# tides_v40.net
KiCad netlist of a schematic drawn in EAGLE
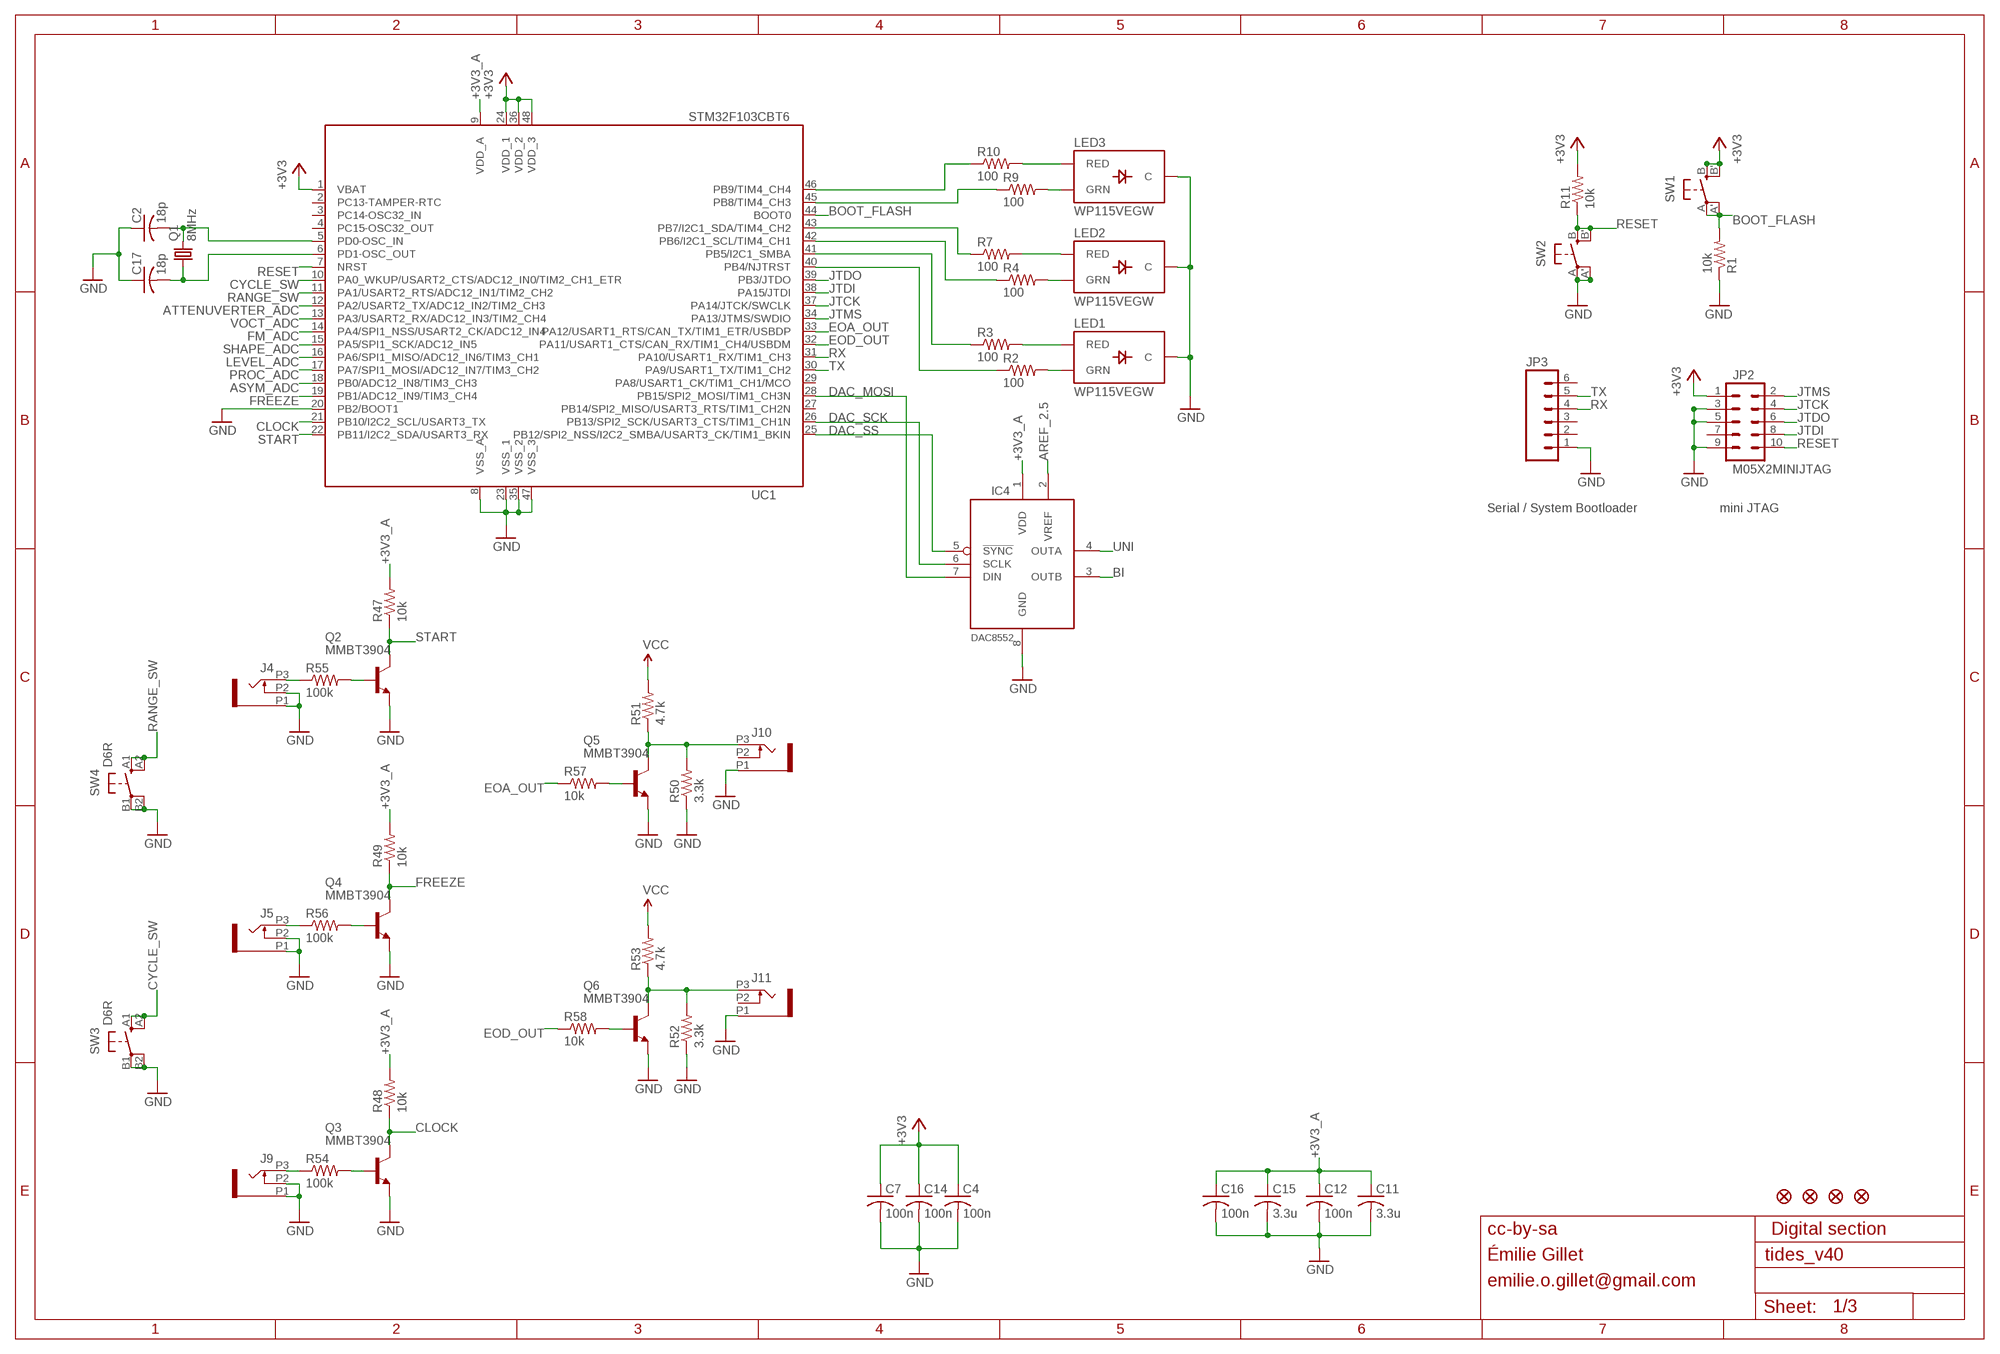
[diagram p0: schematic, sheet 1]
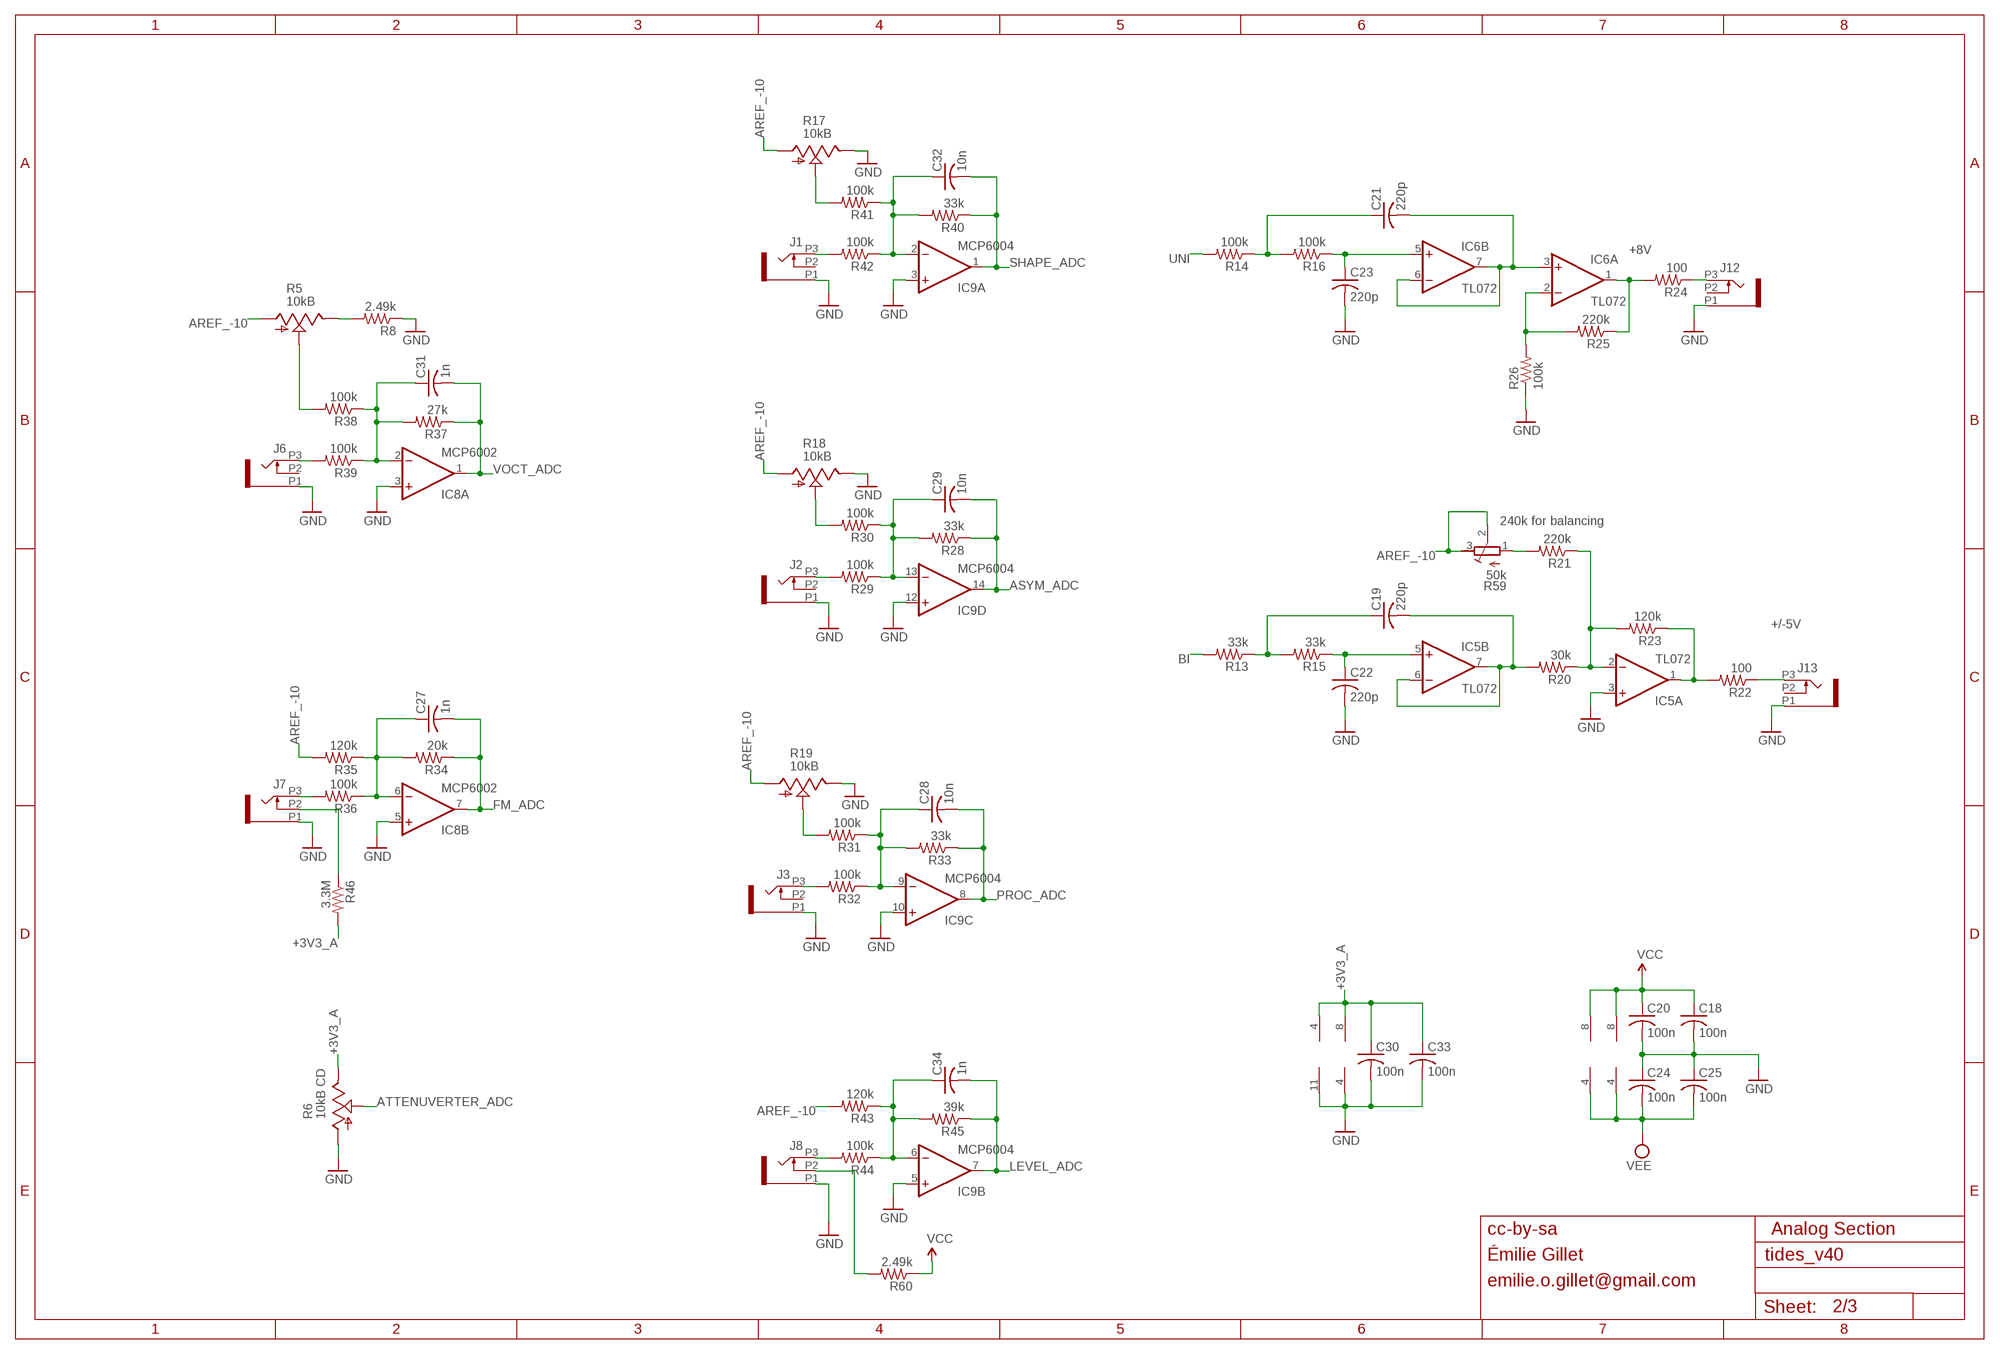
[diagram p1: schematic, sheet 2]
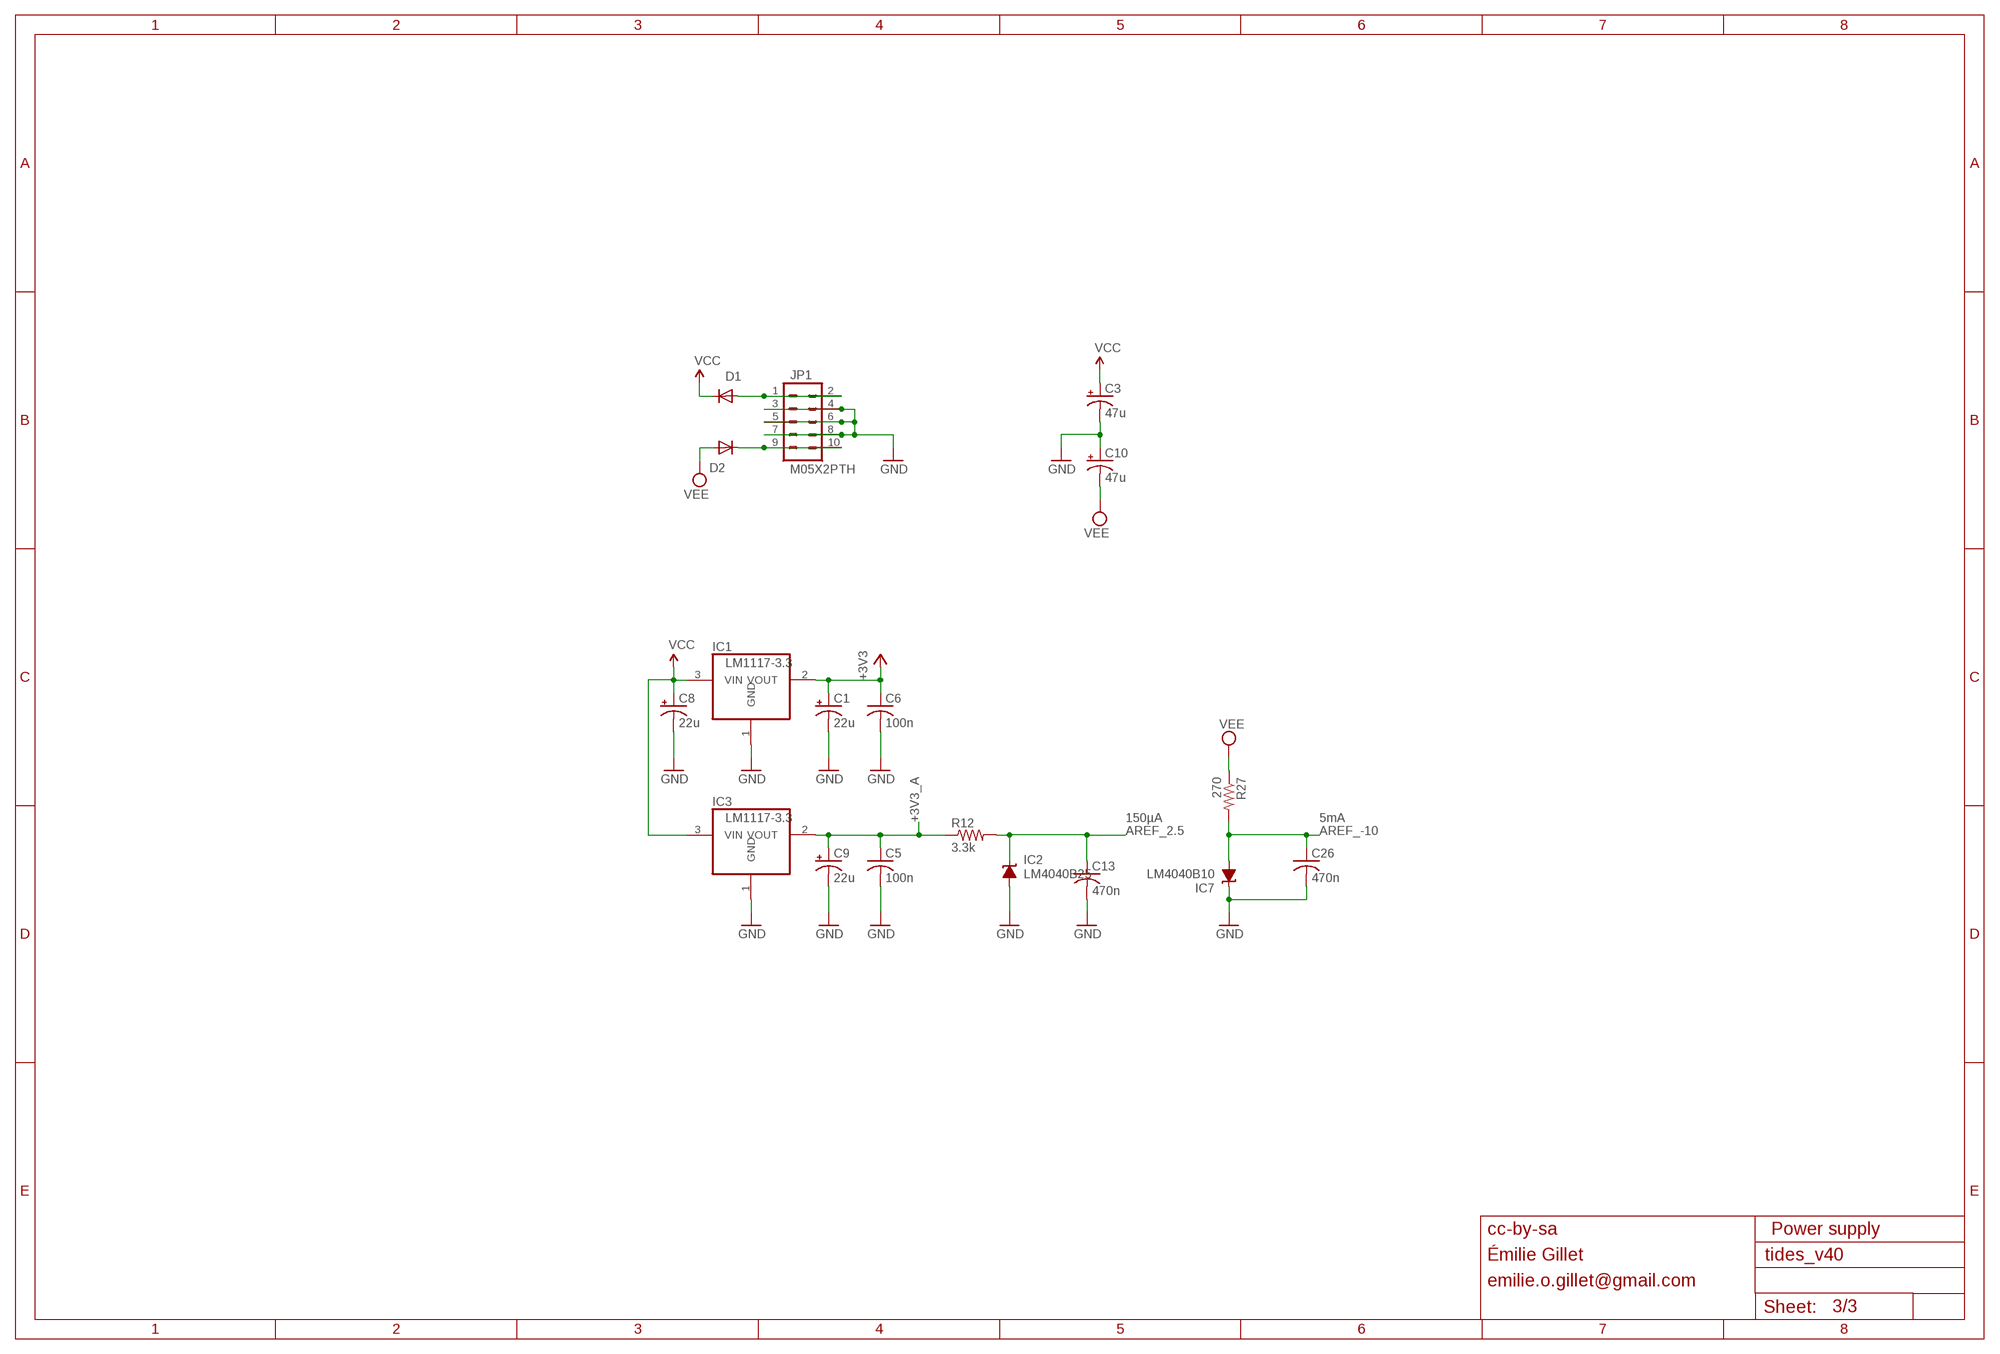
[diagram p2: schematic, sheet 3]

(export (version "E")
  (design (tool "Eeschema 10.0.6"))
  (components
    (comp (ref "C2")
      (value "18p")
      (footprint "eagle-import:C0603")
      (libsource (lib "eagle-import") (part "C-USC0603"))
    )
    (comp (ref "C4")
      (value "100n")
      (footprint "eagle-import:C0603")
      (libsource (lib "eagle-import") (part "C-USC0603"))
    )
    (comp (ref "C7")
      (value "100n")
      (footprint "eagle-import:C0603")
      (libsource (lib "eagle-import") (part "C-USC0603"))
    )
    (comp (ref "C11")
      (value "3.3u")
      (footprint "eagle-import:C0603")
      (libsource (lib "eagle-import") (part "C-USC0603"))
    )
    (comp (ref "C12")
      (value "100n")
      (footprint "eagle-import:C0603")
      (libsource (lib "eagle-import") (part "C-USC0603"))
    )
    (comp (ref "C14")
      (value "100n")
      (footprint "eagle-import:C0603")
      (libsource (lib "eagle-import") (part "C-USC0603"))
    )
    (comp (ref "C15")
      (value "3.3u")
      (footprint "eagle-import:C0603")
      (libsource (lib "eagle-import") (part "C-USC0603"))
    )
    (comp (ref "C16")
      (value "100n")
      (footprint "eagle-import:C0603")
      (libsource (lib "eagle-import") (part "C-USC0603"))
    )
    (comp (ref "C17")
      (value "18p")
      (footprint "eagle-import:C0603")
      (libsource (lib "eagle-import") (part "C-USC0603"))
    )
    (comp (ref "IC4")
      (value "DAC8552")
      (footprint "eagle-import:MSOP-8")
      (libsource (lib "eagle-import") (part "DAC8552"))
    )
    (comp (ref "J4")
      (value "PJ301_THONKICONN6")
      (footprint "eagle-import:WQP_PJ_301M6")
      (libsource (lib "eagle-import") (part "PJ301_THONKICONN6"))
    )
    (comp (ref "J5")
      (value "PJ301_THONKICONN6")
      (footprint "eagle-import:WQP_PJ_301M6")
      (libsource (lib "eagle-import") (part "PJ301_THONKICONN6"))
    )
    (comp (ref "J9")
      (value "PJ301_THONKICONN6")
      (footprint "eagle-import:WQP_PJ_301M6")
      (libsource (lib "eagle-import") (part "PJ301_THONKICONN6"))
    )
    (comp (ref "J10")
      (value "PJ301_THONKICONN6")
      (footprint "eagle-import:WQP_PJ_301M6")
      (libsource (lib "eagle-import") (part "PJ301_THONKICONN6"))
    )
    (comp (ref "J11")
      (value "PJ301_THONKICONN6")
      (footprint "eagle-import:WQP_PJ_301M6")
      (libsource (lib "eagle-import") (part "PJ301_THONKICONN6"))
    )
    (comp (ref "JP2")
      (value "M05X2MINIJTAG")
      (footprint "eagle-import:2X5-1.27")
      (libsource (lib "eagle-import") (part "M05X2MINIJTAG"))
    )
    (comp (ref "JP3")
      (value "M06SIP")
      (footprint "eagle-import:1X06")
      (libsource (lib "eagle-import") (part "M06SIP"))
    )
    (comp (ref "JP4")
      (value "FIDUCIAL1X2")
      (footprint "eagle-import:FIDUCIAL-1X2")
      (libsource (lib "eagle-import") (part "FIDUCIAL1X2"))
    )
    (comp (ref "JP5")
      (value "FIDUCIAL1X2")
      (footprint "eagle-import:FIDUCIAL-1X2")
      (libsource (lib "eagle-import") (part "FIDUCIAL1X2"))
    )
    (comp (ref "JP6")
      (value "FIDUCIAL1X2")
      (footprint "eagle-import:FIDUCIAL-1X2")
      (libsource (lib "eagle-import") (part "FIDUCIAL1X2"))
    )
    (comp (ref "JP7")
      (value "FIDUCIAL1X2")
      (footprint "eagle-import:FIDUCIAL-1X2")
      (libsource (lib "eagle-import") (part "FIDUCIAL1X2"))
    )
    (comp (ref "LED1")
      (value "WP115VEGW")
      (footprint "eagle-import:LED-BICOLOR-THROUGHHOLE")
      (libsource (lib "eagle-import") (part "LED-BICOLOR-THROUGHHOLE"))
    )
    (comp (ref "LED2")
      (value "WP115VEGW")
      (footprint "eagle-import:LED-BICOLOR-THROUGHHOLE")
      (libsource (lib "eagle-import") (part "LED-BICOLOR-THROUGHHOLE"))
    )
    (comp (ref "LED3")
      (value "WP115VEGW")
      (footprint "eagle-import:LED-BICOLOR-THROUGHHOLE")
      (libsource (lib "eagle-import") (part "LED-BICOLOR-THROUGHHOLE"))
    )
    (comp (ref "Q1")
      (value "8MHz")
      (footprint "eagle-import:HC49UP")
      (libsource (lib "eagle-import") (part "CRYSTALHC49UP"))
    )
    (comp (ref "Q2")
      (value "MMBT3904")
      (footprint "eagle-import:SOT23-BEC")
      (libsource (lib "eagle-import") (part "-NPN-SOT23-BECMMBT3904LT1"))
    )
    (comp (ref "Q3")
      (value "MMBT3904")
      (footprint "eagle-import:SOT23-BEC")
      (libsource (lib "eagle-import") (part "-NPN-SOT23-BECMMBT3904LT1"))
    )
    (comp (ref "Q4")
      (value "MMBT3904")
      (footprint "eagle-import:SOT23-BEC")
      (libsource (lib "eagle-import") (part "-NPN-SOT23-BECMMBT3904LT1"))
    )
    (comp (ref "Q5")
      (value "MMBT3904")
      (footprint "eagle-import:SOT23-BEC")
      (libsource (lib "eagle-import") (part "-NPN-SOT23-BECMMBT3904LT1"))
    )
    (comp (ref "Q6")
      (value "MMBT3904")
      (footprint "eagle-import:SOT23-BEC")
      (libsource (lib "eagle-import") (part "-NPN-SOT23-BECMMBT3904LT1"))
    )
    (comp (ref "R1")
      (value "10k")
      (footprint "eagle-import:R0603")
      (libsource (lib "eagle-import") (part "R-US_R0603"))
    )
    (comp (ref "R2")
      (value "100")
      (footprint "eagle-import:R0603")
      (libsource (lib "eagle-import") (part "R-US_R0603"))
    )
    (comp (ref "R3")
      (value "100")
      (footprint "eagle-import:R0603")
      (libsource (lib "eagle-import") (part "R-US_R0603"))
    )
    (comp (ref "R4")
      (value "100")
      (footprint "eagle-import:R0603")
      (libsource (lib "eagle-import") (part "R-US_R0603"))
    )
    (comp (ref "R7")
      (value "100")
      (footprint "eagle-import:R0603")
      (libsource (lib "eagle-import") (part "R-US_R0603"))
    )
    (comp (ref "R9")
      (value "100")
      (footprint "eagle-import:R0603")
      (libsource (lib "eagle-import") (part "R-US_R0603"))
    )
    (comp (ref "R10")
      (value "100")
      (footprint "eagle-import:R0603")
      (libsource (lib "eagle-import") (part "R-US_R0603"))
    )
    (comp (ref "R11")
      (value "10k")
      (footprint "eagle-import:R0603")
      (libsource (lib "eagle-import") (part "R-US_R0603"))
    )
    (comp (ref "R47")
      (value "10k")
      (footprint "eagle-import:R0603")
      (libsource (lib "eagle-import") (part "R-US_R0603"))
    )
    (comp (ref "R48")
      (value "10k")
      (footprint "eagle-import:R0603")
      (libsource (lib "eagle-import") (part "R-US_R0603"))
    )
    (comp (ref "R49")
      (value "10k")
      (footprint "eagle-import:R0603")
      (libsource (lib "eagle-import") (part "R-US_R0603"))
    )
    (comp (ref "R50")
      (value "3.3k")
      (footprint "eagle-import:R0603")
      (libsource (lib "eagle-import") (part "R-US_R0603"))
    )
    (comp (ref "R51")
      (value "4.7k")
      (footprint "eagle-import:R0603")
      (libsource (lib "eagle-import") (part "R-US_R0603"))
    )
    (comp (ref "R52")
      (value "3.3k")
      (footprint "eagle-import:R0603")
      (libsource (lib "eagle-import") (part "R-US_R0603"))
    )
    (comp (ref "R53")
      (value "4.7k")
      (footprint "eagle-import:R0603")
      (libsource (lib "eagle-import") (part "R-US_R0603"))
    )
    (comp (ref "R54")
      (value "100k")
      (footprint "eagle-import:R0603")
      (libsource (lib "eagle-import") (part "R-US_R0603"))
    )
    (comp (ref "R55")
      (value "100k")
      (footprint "eagle-import:R0603")
      (libsource (lib "eagle-import") (part "R-US_R0603"))
    )
    (comp (ref "R56")
      (value "100k")
      (footprint "eagle-import:R0603")
      (libsource (lib "eagle-import") (part "R-US_R0603"))
    )
    (comp (ref "R57")
      (value "10k")
      (footprint "eagle-import:R0603")
      (libsource (lib "eagle-import") (part "R-US_R0603"))
    )
    (comp (ref "R58")
      (value "10k")
      (footprint "eagle-import:R0603")
      (libsource (lib "eagle-import") (part "R-US_R0603"))
    )
    (comp (ref "SW1")
      (value "EVQQ2")
      (footprint "eagle-import:EVQ-Q2")
      (libsource (lib "eagle-import") (part "EVQQ2"))
    )
    (comp (ref "SW2")
      (value "EVQQ2")
      (footprint "eagle-import:EVQ-Q2")
      (libsource (lib "eagle-import") (part "EVQQ2"))
    )
    (comp (ref "SW3")
      (value "D6R")
      (footprint "eagle-import:D6R")
      (libsource (lib "eagle-import") (part "D6R"))
    )
    (comp (ref "SW4")
      (value "D6R")
      (footprint "eagle-import:D6R")
      (libsource (lib "eagle-import") (part "D6R"))
    )
    (comp (ref "UC1")
      (value "STM32F103CBT6")
      (footprint "eagle-import:LQFP48")
      (libsource (lib "eagle-import") (part "STM32F103CB"))
    )
    (comp (ref "C18")
      (value "100n")
      (footprint "eagle-import:C0603")
      (libsource (lib "eagle-import") (part "C-USC0603"))
    )
    (comp (ref "C19")
      (value "220p")
      (footprint "eagle-import:C0603")
      (libsource (lib "eagle-import") (part "C-USC0603"))
    )
    (comp (ref "C20")
      (value "100n")
      (footprint "eagle-import:C0603")
      (libsource (lib "eagle-import") (part "C-USC0603"))
    )
    (comp (ref "C21")
      (value "220p")
      (footprint "eagle-import:C0603")
      (libsource (lib "eagle-import") (part "C-USC0603"))
    )
    (comp (ref "C22")
      (value "220p")
      (footprint "eagle-import:C0603")
      (libsource (lib "eagle-import") (part "C-USC0603"))
    )
    (comp (ref "C23")
      (value "220p")
      (footprint "eagle-import:C0603")
      (libsource (lib "eagle-import") (part "C-USC0603"))
    )
    (comp (ref "C24")
      (value "100n")
      (footprint "eagle-import:C0603")
      (libsource (lib "eagle-import") (part "C-USC0603"))
    )
    (comp (ref "C25")
      (value "100n")
      (footprint "eagle-import:C0603")
      (libsource (lib "eagle-import") (part "C-USC0603"))
    )
    (comp (ref "C27")
      (value "1n")
      (footprint "eagle-import:C0603")
      (libsource (lib "eagle-import") (part "C-USC0603"))
    )
    (comp (ref "C28")
      (value "10n")
      (footprint "eagle-import:C0603")
      (libsource (lib "eagle-import") (part "C-USC0603"))
    )
    (comp (ref "C29")
      (value "10n")
      (footprint "eagle-import:C0603")
      (libsource (lib "eagle-import") (part "C-USC0603"))
    )
    (comp (ref "C30")
      (value "100n")
      (footprint "eagle-import:C0603")
      (libsource (lib "eagle-import") (part "C-USC0603"))
    )
    (comp (ref "C31")
      (value "1n")
      (footprint "eagle-import:C0603")
      (libsource (lib "eagle-import") (part "C-USC0603"))
    )
    (comp (ref "C32")
      (value "10n")
      (footprint "eagle-import:C0603")
      (libsource (lib "eagle-import") (part "C-USC0603"))
    )
    (comp (ref "C33")
      (value "100n")
      (footprint "eagle-import:C0603")
      (libsource (lib "eagle-import") (part "C-USC0603"))
    )
    (comp (ref "C34")
      (value "1n")
      (footprint "eagle-import:C0603")
      (libsource (lib "eagle-import") (part "C-USC0603"))
    )
    (comp (ref "IC5")
      (value "TL072")
      (footprint "eagle-import:SO08")
      (libsource (lib "eagle-import") (part "TL072D"))
    )
    (comp (ref "IC6")
      (value "TL072")
      (footprint "eagle-import:SO08")
      (libsource (lib "eagle-import") (part "TL072D"))
    )
    (comp (ref "IC8")
      (value "MCP6002")
      (footprint "eagle-import:SO08")
      (libsource (lib "eagle-import") (part "TL072D"))
    )
    (comp (ref "IC9")
      (value "MCP6004")
      (footprint "eagle-import:SO14")
      (libsource (lib "eagle-import") (part "TL074D"))
    )
    (comp (ref "J1")
      (value "PJ301_THONKICONN6")
      (footprint "eagle-import:WQP_PJ_301M6")
      (libsource (lib "eagle-import") (part "PJ301_THONKICONN6"))
    )
    (comp (ref "J2")
      (value "PJ301_THONKICONN6")
      (footprint "eagle-import:WQP_PJ_301M6")
      (libsource (lib "eagle-import") (part "PJ301_THONKICONN6"))
    )
    (comp (ref "J3")
      (value "PJ301_THONKICONN6")
      (footprint "eagle-import:WQP_PJ_301M6")
      (libsource (lib "eagle-import") (part "PJ301_THONKICONN6"))
    )
    (comp (ref "J6")
      (value "PJ301_THONKICONN6")
      (footprint "eagle-import:WQP_PJ_301M6")
      (libsource (lib "eagle-import") (part "PJ301_THONKICONN6"))
    )
    (comp (ref "J7")
      (value "PJ301_THONKICONN6")
      (footprint "eagle-import:WQP_PJ_301M6")
      (libsource (lib "eagle-import") (part "PJ301_THONKICONN6"))
    )
    (comp (ref "J8")
      (value "PJ301_THONKICONN6")
      (footprint "eagle-import:WQP_PJ_301M6")
      (libsource (lib "eagle-import") (part "PJ301_THONKICONN6"))
    )
    (comp (ref "J12")
      (value "PJ301_THONKICONN6")
      (footprint "eagle-import:WQP_PJ_301M6")
      (libsource (lib "eagle-import") (part "PJ301_THONKICONN6"))
    )
    (comp (ref "J13")
      (value "PJ301_THONKICONN6")
      (footprint "eagle-import:WQP_PJ_301M6")
      (libsource (lib "eagle-import") (part "PJ301_THONKICONN6"))
    )
    (comp (ref "R5")
      (value "10kB")
      (footprint "eagle-import:ALPS_POT_VERTICAL_PS")
      (libsource (lib "eagle-import") (part "POT_USVERTICAL_PS"))
    )
    (comp (ref "R6")
      (value "10kB CD")
      (footprint "eagle-import:ALPS_POT_VERTICAL_PS")
      (libsource (lib "eagle-import") (part "POT_USVERTICAL_PS"))
    )
    (comp (ref "R8")
      (value "2.49k")
      (footprint "eagle-import:R0603")
      (libsource (lib "eagle-import") (part "R-US_R0603"))
    )
    (comp (ref "R13")
      (value "33k")
      (footprint "eagle-import:R0603")
      (libsource (lib "eagle-import") (part "R-US_R0603"))
    )
    (comp (ref "R14")
      (value "100k")
      (footprint "eagle-import:R0603")
      (libsource (lib "eagle-import") (part "R-US_R0603"))
    )
    (comp (ref "R15")
      (value "33k")
      (footprint "eagle-import:R0603")
      (libsource (lib "eagle-import") (part "R-US_R0603"))
    )
    (comp (ref "R16")
      (value "100k")
      (footprint "eagle-import:R0603")
      (libsource (lib "eagle-import") (part "R-US_R0603"))
    )
    (comp (ref "R17")
      (value "10kB")
      (footprint "eagle-import:ALPS_POT_VERTICAL_PS")
      (libsource (lib "eagle-import") (part "POT_USVERTICAL_PS"))
    )
    (comp (ref "R18")
      (value "10kB")
      (footprint "eagle-import:ALPS_POT_VERTICAL_PS")
      (libsource (lib "eagle-import") (part "POT_USVERTICAL_PS"))
    )
    (comp (ref "R19")
      (value "10kB")
      (footprint "eagle-import:ALPS_POT_VERTICAL_PS")
      (libsource (lib "eagle-import") (part "POT_USVERTICAL_PS"))
    )
    (comp (ref "R20")
      (value "30k")
      (footprint "eagle-import:R0603")
      (libsource (lib "eagle-import") (part "R-US_R0603"))
    )
    (comp (ref "R21")
      (value "220k")
      (footprint "eagle-import:R0603")
      (libsource (lib "eagle-import") (part "R-US_R0603"))
    )
    (comp (ref "R22")
      (value "100")
      (footprint "eagle-import:R0603")
      (libsource (lib "eagle-import") (part "R-US_R0603"))
    )
    (comp (ref "R23")
      (value "120k")
      (footprint "eagle-import:R0603")
      (libsource (lib "eagle-import") (part "R-US_R0603"))
    )
    (comp (ref "R24")
      (value "100")
      (footprint "eagle-import:R0603")
      (libsource (lib "eagle-import") (part "R-US_R0603"))
    )
    (comp (ref "R25")
      (value "220k")
      (footprint "eagle-import:R0603")
      (libsource (lib "eagle-import") (part "R-US_R0603"))
    )
    (comp (ref "R26")
      (value "100k")
      (footprint "eagle-import:R0603")
      (libsource (lib "eagle-import") (part "R-US_R0603"))
    )
    (comp (ref "R28")
      (value "33k")
      (footprint "eagle-import:R0603")
      (libsource (lib "eagle-import") (part "R-US_R0603"))
    )
    (comp (ref "R29")
      (value "100k")
      (footprint "eagle-import:R0603")
      (libsource (lib "eagle-import") (part "R-US_R0603"))
    )
    (comp (ref "R30")
      (value "100k")
      (footprint "eagle-import:R0603")
      (libsource (lib "eagle-import") (part "R-US_R0603"))
    )
    (comp (ref "R31")
      (value "100k")
      (footprint "eagle-import:R0603")
      (libsource (lib "eagle-import") (part "R-US_R0603"))
    )
    (comp (ref "R32")
      (value "100k")
      (footprint "eagle-import:R0603")
      (libsource (lib "eagle-import") (part "R-US_R0603"))
    )
    (comp (ref "R33")
      (value "33k")
      (footprint "eagle-import:R0603")
      (libsource (lib "eagle-import") (part "R-US_R0603"))
    )
    (comp (ref "R34")
      (value "20k")
      (footprint "eagle-import:R0603")
      (libsource (lib "eagle-import") (part "R-US_R0603"))
    )
    (comp (ref "R35")
      (value "120k")
      (footprint "eagle-import:R0603")
      (libsource (lib "eagle-import") (part "R-US_R0603"))
    )
    (comp (ref "R36")
      (value "100k")
      (footprint "eagle-import:R0603")
      (libsource (lib "eagle-import") (part "R-US_R0603"))
    )
    (comp (ref "R37")
      (value "27k")
      (footprint "eagle-import:R0603")
      (libsource (lib "eagle-import") (part "R-US_R0603"))
    )
    (comp (ref "R38")
      (value "100k")
      (footprint "eagle-import:R0603")
      (libsource (lib "eagle-import") (part "R-US_R0603"))
    )
    (comp (ref "R39")
      (value "100k")
      (footprint "eagle-import:R0603")
      (libsource (lib "eagle-import") (part "R-US_R0603"))
    )
    (comp (ref "R40")
      (value "33k")
      (footprint "eagle-import:R0603")
      (libsource (lib "eagle-import") (part "R-US_R0603"))
    )
    (comp (ref "R41")
      (value "100k")
      (footprint "eagle-import:R0603")
      (libsource (lib "eagle-import") (part "R-US_R0603"))
    )
    (comp (ref "R42")
      (value "100k")
      (footprint "eagle-import:R0603")
      (libsource (lib "eagle-import") (part "R-US_R0603"))
    )
    (comp (ref "R43")
      (value "120k")
      (footprint "eagle-import:R0603")
      (libsource (lib "eagle-import") (part "R-US_R0603"))
    )
    (comp (ref "R44")
      (value "100k")
      (footprint "eagle-import:R0603")
      (libsource (lib "eagle-import") (part "R-US_R0603"))
    )
    (comp (ref "R45")
      (value "39k")
      (footprint "eagle-import:R0603")
      (libsource (lib "eagle-import") (part "R-US_R0603"))
    )
    (comp (ref "R46")
      (value "3.3M")
      (footprint "eagle-import:R0603")
      (libsource (lib "eagle-import") (part "R-US_R0603"))
    )
    (comp (ref "R59")
      (value "50k")
      (footprint "eagle-import:RTRIM3296X")
      (libsource (lib "eagle-import") (part "R-TRIMM3296X"))
    )
    (comp (ref "R60")
      (value "2.49k")
      (footprint "eagle-import:R0805")
      (libsource (lib "eagle-import") (part "R-US_R0805"))
    )
    (comp (ref "C1")
      (value "22u")
      (footprint "eagle-import:PANASONIC_C")
      (libsource (lib "eagle-import") (part "CPOL-USC"))
    )
    (comp (ref "C3")
      (value "47u")
      (footprint "eagle-import:PANASONIC_D")
      (libsource (lib "eagle-import") (part "CPOL-USD"))
    )
    (comp (ref "C5")
      (value "100n")
      (footprint "eagle-import:C0603")
      (libsource (lib "eagle-import") (part "C-USC0603"))
    )
    (comp (ref "C6")
      (value "100n")
      (footprint "eagle-import:C0603")
      (libsource (lib "eagle-import") (part "C-USC0603"))
    )
    (comp (ref "C8")
      (value "22u")
      (footprint "eagle-import:PANASONIC_C")
      (libsource (lib "eagle-import") (part "CPOL-USC"))
    )
    (comp (ref "C9")
      (value "22u")
      (footprint "eagle-import:PANASONIC_C")
      (libsource (lib "eagle-import") (part "CPOL-USC"))
    )
    (comp (ref "C10")
      (value "47u")
      (footprint "eagle-import:PANASONIC_D")
      (libsource (lib "eagle-import") (part "CPOL-USD"))
    )
    (comp (ref "C13")
      (value "470n")
      (footprint "eagle-import:C0603")
      (libsource (lib "eagle-import") (part "C-USC0603"))
    )
    (comp (ref "C26")
      (value "470n")
      (footprint "eagle-import:C0603")
      (libsource (lib "eagle-import") (part "C-USC0603"))
    )
    (comp (ref "D1")
      (value "1N5819HW")
      (footprint "eagle-import:SOD123")
      (libsource (lib "eagle-import") (part "DIODE-SOD123"))
    )
    (comp (ref "D2")
      (value "1N5819HW")
      (footprint "eagle-import:SOD123")
      (libsource (lib "eagle-import") (part "DIODE-SOD123"))
    )
    (comp (ref "IC1")
      (value "LM1117-3.3")
      (footprint "eagle-import:SOT223")
      (libsource (lib "eagle-import") (part "REG1117"))
    )
    (comp (ref "IC2")
      (value "LM4040B25")
      (footprint "eagle-import:DBZ_R-PDSO-G3")
      (libsource (lib "eagle-import") (part "LM4041DBZB12"))
    )
    (comp (ref "IC3")
      (value "LM1117-3.3")
      (footprint "eagle-import:SOT223")
      (libsource (lib "eagle-import") (part "REG1117"))
    )
    (comp (ref "IC7")
      (value "LM4040B10")
      (footprint "eagle-import:DBZ_R-PDSO-G3")
      (libsource (lib "eagle-import") (part "LM4041DBZB12"))
    )
    (comp (ref "JP1")
      (value "M05X2PTH")
      (footprint "eagle-import:AVR_ICSP")
      (libsource (lib "eagle-import") (part "M05X2PTH"))
    )
    (comp (ref "R12")
      (value "3.3k")
      (footprint "eagle-import:R0603")
      (libsource (lib "eagle-import") (part "R-US_R0603"))
    )
    (comp (ref "R27")
      (value "270")
      (footprint "eagle-import:R0603")
      (libsource (lib "eagle-import") (part "R-US_R0603"))
    )
  )
  (nets
    (net (code "1") (name "+3V3") (class "Default")
      (node (ref "C1") (pin "+") (pinfunction "+_+") (pintype "passive"))
      (node (ref "C14") (pin "1") (pinfunction "1_1") (pintype "passive"))
      (node (ref "C4") (pin "1") (pinfunction "1_1") (pintype "passive"))
      (node (ref "C6") (pin "1") (pinfunction "1_1") (pintype "passive"))
      (node (ref "C7") (pin "1") (pinfunction "1_1") (pintype "passive"))
      (node (ref "IC1") (pin "2") (pinfunction "VOUT_2") (pintype "output"))
      (node (ref "JP2") (pin "1") (pinfunction "1_1") (pintype "passive"))
      (node (ref "R11") (pin "2") (pinfunction "2_2") (pintype "passive"))
      (node (ref "SW1") (pin "B") (pinfunction "S_B") (pintype "passive"))
      (node (ref "SW1") (pin "B'") (pinfunction "S1_B'") (pintype "passive"))
      (node (ref "UC1") (pin "1") (pinfunction "VBAT_1") (pintype "power_in"))
      (node (ref "UC1") (pin "24") (pinfunction "VDD_1_24") (pintype "power_in"))
      (node (ref "UC1") (pin "36") (pinfunction "VDD_2_36") (pintype "power_in"))
      (node (ref "UC1") (pin "48") (pinfunction "VDD_3_48") (pintype "power_in"))
    )
    (net (code "2") (name "+3V3_A") (class "Default")
      (node (ref "C11") (pin "1") (pinfunction "1_1") (pintype "passive"))
      (node (ref "C12") (pin "1") (pinfunction "1_1") (pintype "passive"))
      (node (ref "C15") (pin "1") (pinfunction "1_1") (pintype "passive"))
      (node (ref "C16") (pin "1") (pinfunction "1_1") (pintype "passive"))
      (node (ref "C30") (pin "1") (pinfunction "1_1") (pintype "passive"))
      (node (ref "C33") (pin "1") (pinfunction "1_1") (pintype "passive"))
      (node (ref "C5") (pin "1") (pinfunction "1_1") (pintype "passive"))
      (node (ref "C9") (pin "+") (pinfunction "+_+") (pintype "passive"))
      (node (ref "IC3") (pin "2") (pinfunction "VOUT_2") (pintype "output"))
      (node (ref "IC4") (pin "1") (pinfunction "VDD_1") (pintype "power_in"))
      (node (ref "IC8") (pin "8") (pinfunction "V+_8") (pintype "power_in"))
      (node (ref "IC9") (pin "4") (pinfunction "V+_4") (pintype "power_in"))
      (node (ref "R12") (pin "1") (pinfunction "1_1") (pintype "passive"))
      (node (ref "R46") (pin "2") (pinfunction "2_2") (pintype "passive"))
      (node (ref "R47") (pin "2") (pinfunction "2_2") (pintype "passive"))
      (node (ref "R48") (pin "2") (pinfunction "2_2") (pintype "passive"))
      (node (ref "R49") (pin "2") (pinfunction "2_2") (pintype "passive"))
      (node (ref "R6") (pin "P$1") (pinfunction "E_P$1") (pintype "passive"))
      (node (ref "UC1") (pin "9") (pinfunction "VDD_A_9") (pintype "power_in"))
    )
    (net (code "3") (name "AREF_-10") (class "Default")
      (node (ref "C26") (pin "1") (pinfunction "1_1") (pintype "passive"))
      (node (ref "IC7") (pin "2") (pinfunction "A_2") (pintype "passive"))
      (node (ref "R17") (pin "P$3") (pinfunction "A_P$3") (pintype "passive"))
      (node (ref "R18") (pin "P$3") (pinfunction "A_P$3") (pintype "passive"))
      (node (ref "R19") (pin "P$3") (pinfunction "A_P$3") (pintype "passive"))
      (node (ref "R27") (pin "2") (pinfunction "2_2") (pintype "passive"))
      (node (ref "R35") (pin "2") (pinfunction "2_2") (pintype "passive"))
      (node (ref "R43") (pin "2") (pinfunction "2_2") (pintype "passive"))
      (node (ref "R5") (pin "P$3") (pinfunction "A_P$3") (pintype "passive"))
      (node (ref "R59") (pin "2") (pinfunction "S_2") (pintype "passive"))
      (node (ref "R59") (pin "3") (pinfunction "A_3") (pintype "passive"))
    )
    (net (code "4") (name "AREF_2.5") (class "Default")
      (node (ref "C13") (pin "1") (pinfunction "1_1") (pintype "passive"))
      (node (ref "IC2") (pin "1") (pinfunction "C_1") (pintype "passive"))
      (node (ref "IC4") (pin "2") (pinfunction "VREF_2") (pintype "power_in"))
      (node (ref "R12") (pin "2") (pinfunction "2_2") (pintype "passive"))
    )
    (net (code "5") (name "ASYM_ADC") (class "Default")
      (node (ref "C29") (pin "2") (pinfunction "2_2") (pintype "passive"))
      (node (ref "IC9") (pin "14") (pinfunction "OUT_14") (pintype "output"))
      (node (ref "R28") (pin "1") (pinfunction "1_1") (pintype "passive"))
      (node (ref "UC1") (pin "18") (pinfunction "PB0/ADC12_IN8/TIM3_CH3_18") (pintype "bidirectional"))
    )
    (net (code "6") (name "ATTENUVERTER_ADC") (class "Default")
      (node (ref "R6") (pin "P$2") (pinfunction "S_P$2") (pintype "passive"))
      (node (ref "UC1") (pin "12") (pinfunction "PA2/USART2_TX/ADC12_IN2/TIM2_CH3_12") (pintype "bidirectional"))
    )
    (net (code "7") (name "BI") (class "Default")
      (node (ref "IC4") (pin "3") (pinfunction "OUTB_3") (pintype "input"))
      (node (ref "R13") (pin "2") (pinfunction "2_2") (pintype "passive"))
    )
    (net (code "8") (name "BOOT_FLASH") (class "Default")
      (node (ref "R1") (pin "2") (pinfunction "2_2") (pintype "passive"))
      (node (ref "SW1") (pin "A") (pinfunction "P_A") (pintype "passive"))
      (node (ref "SW1") (pin "A'") (pinfunction "P1_A'") (pintype "passive"))
      (node (ref "UC1") (pin "44") (pinfunction "BOOT0_44") (pintype "input"))
    )
    (net (code "9") (name "CLOCK") (class "Default")
      (node (ref "Q3") (pin "C") (pinfunction "C_C") (pintype "passive"))
      (node (ref "R48") (pin "1") (pinfunction "1_1") (pintype "passive"))
      (node (ref "UC1") (pin "21") (pinfunction "PB10/I2C2_SCL/USART3_TX_21") (pintype "input"))
    )
    (net (code "10") (name "CYCLE_SW") (class "Default")
      (node (ref "SW3") (pin "A1") (pinfunction "S_A1") (pintype "passive"))
      (node (ref "SW3") (pin "A2") (pinfunction "S1_A2") (pintype "passive"))
      (node (ref "UC1") (pin "10") (pinfunction "PA0_WKUP/USART2_CTS/ADC12_IN0/TIM2_CH1_ETR_10") (pintype "bidirectional"))
    )
    (net (code "11") (name "DAC_MOSI") (class "Default")
      (node (ref "IC4") (pin "7") (pinfunction "DIN_7") (pintype "bidirectional"))
      (node (ref "UC1") (pin "28") (pinfunction "PB15/SPI2_MOSI/TIM1_CH3N_28") (pintype "input"))
    )
    (net (code "12") (name "DAC_SCK") (class "Default")
      (node (ref "IC4") (pin "6") (pinfunction "SCLK_6") (pintype "bidirectional"))
      (node (ref "UC1") (pin "26") (pinfunction "PB13/SPI2_SCK/USART3_CTS/TIM1_CH1N_26") (pintype "input"))
    )
    (net (code "13") (name "DAC_SS") (class "Default")
      (node (ref "IC4") (pin "5") (pinfunction "~{SYNC}_5") (pintype "bidirectional"))
      (node (ref "UC1") (pin "25") (pinfunction "PB12/SPI2_NSS/I2C2_SMBA/USART3_CK/TIM1_BKIN_25") (pintype "input"))
    )
    (net (code "14") (name "EOA_OUT") (class "Default")
      (node (ref "R57") (pin "1") (pinfunction "1_1") (pintype "passive"))
      (node (ref "UC1") (pin "33") (pinfunction "PA12/USART1_RTS/CAN_TX/TIM1_ETR/USBDP_33") (pintype "bidirectional"))
    )
    (net (code "15") (name "EOD_OUT") (class "Default")
      (node (ref "R58") (pin "1") (pinfunction "1_1") (pintype "passive"))
      (node (ref "UC1") (pin "32") (pinfunction "PA11/USART1_CTS/CAN_RX/TIM1_CH4/USBDM_32") (pintype "bidirectional"))
    )
    (net (code "16") (name "FM_ADC") (class "Default")
      (node (ref "C27") (pin "2") (pinfunction "2_2") (pintype "passive"))
      (node (ref "IC8") (pin "7") (pinfunction "OUT_7") (pintype "output"))
      (node (ref "R34") (pin "1") (pinfunction "1_1") (pintype "passive"))
      (node (ref "UC1") (pin "14") (pinfunction "PA4/SPI1_NSS/USART2_CK/ADC12_IN4_14") (pintype "bidirectional"))
    )
    (net (code "17") (name "FREEZE") (class "Default")
      (node (ref "Q4") (pin "C") (pinfunction "C_C") (pintype "passive"))
      (node (ref "R49") (pin "1") (pinfunction "1_1") (pintype "passive"))
      (node (ref "UC1") (pin "19") (pinfunction "PB1/ADC12_IN9/TIM3_CH4_19") (pintype "bidirectional"))
    )
    (net (code "18") (name "GND") (class "Default")
      (node (ref "C1") (pin "-") (pinfunction "-_-") (pintype "passive"))
      (node (ref "C10") (pin "+") (pinfunction "+_+") (pintype "passive"))
      (node (ref "C11") (pin "2") (pinfunction "2_2") (pintype "passive"))
      (node (ref "C12") (pin "2") (pinfunction "2_2") (pintype "passive"))
      (node (ref "C13") (pin "2") (pinfunction "2_2") (pintype "passive"))
      (node (ref "C14") (pin "2") (pinfunction "2_2") (pintype "passive"))
      (node (ref "C15") (pin "2") (pinfunction "2_2") (pintype "passive"))
      (node (ref "C16") (pin "2") (pinfunction "2_2") (pintype "passive"))
      (node (ref "C17") (pin "1") (pinfunction "1_1") (pintype "passive"))
      (node (ref "C18") (pin "2") (pinfunction "2_2") (pintype "passive"))
      (node (ref "C2") (pin "1") (pinfunction "1_1") (pintype "passive"))
      (node (ref "C20") (pin "2") (pinfunction "2_2") (pintype "passive"))
      (node (ref "C22") (pin "2") (pinfunction "2_2") (pintype "passive"))
      (node (ref "C23") (pin "2") (pinfunction "2_2") (pintype "passive"))
      (node (ref "C24") (pin "1") (pinfunction "1_1") (pintype "passive"))
      (node (ref "C25") (pin "1") (pinfunction "1_1") (pintype "passive"))
      (node (ref "C26") (pin "2") (pinfunction "2_2") (pintype "passive"))
      (node (ref "C3") (pin "-") (pinfunction "-_-") (pintype "passive"))
      (node (ref "C30") (pin "2") (pinfunction "2_2") (pintype "passive"))
      (node (ref "C33") (pin "2") (pinfunction "2_2") (pintype "passive"))
      (node (ref "C4") (pin "2") (pinfunction "2_2") (pintype "passive"))
      (node (ref "C5") (pin "2") (pinfunction "2_2") (pintype "passive"))
      (node (ref "C6") (pin "2") (pinfunction "2_2") (pintype "passive"))
      (node (ref "C7") (pin "2") (pinfunction "2_2") (pintype "passive"))
      (node (ref "C8") (pin "-") (pinfunction "-_-") (pintype "passive"))
      (node (ref "C9") (pin "-") (pinfunction "-_-") (pintype "passive"))
      (node (ref "IC1") (pin "1") (pinfunction "GND_1") (pintype "power_in"))
      (node (ref "IC2") (pin "2") (pinfunction "A_2") (pintype "passive"))
      (node (ref "IC3") (pin "1") (pinfunction "GND_1") (pintype "power_in"))
      (node (ref "IC4") (pin "8") (pinfunction "GND_8") (pintype "power_in"))
      (node (ref "IC5") (pin "3") (pinfunction "+IN_3") (pintype "input"))
      (node (ref "IC7") (pin "1") (pinfunction "C_1") (pintype "passive"))
      (node (ref "IC8") (pin "3") (pinfunction "+IN_3") (pintype "input"))
      (node (ref "IC8") (pin "4") (pinfunction "V-_4") (pintype "power_in"))
      (node (ref "IC8") (pin "5") (pinfunction "+IN_5") (pintype "input"))
      (node (ref "IC9") (pin "10") (pinfunction "+IN_10") (pintype "input"))
      (node (ref "IC9") (pin "11") (pinfunction "V-_11") (pintype "power_in"))
      (node (ref "IC9") (pin "12") (pinfunction "+IN_12") (pintype "input"))
      (node (ref "IC9") (pin "3") (pinfunction "+IN_3") (pintype "input"))
      (node (ref "IC9") (pin "5") (pinfunction "+IN_5") (pintype "input"))
      (node (ref "J1") (pin "P1") (pinfunction "1_P1") (pintype "passive"))
      (node (ref "J10") (pin "P1") (pinfunction "1_P1") (pintype "passive"))
      (node (ref "J11") (pin "P1") (pinfunction "1_P1") (pintype "passive"))
      (node (ref "J12") (pin "P1") (pinfunction "1_P1") (pintype "passive"))
      (node (ref "J13") (pin "P1") (pinfunction "1_P1") (pintype "passive"))
      (node (ref "J2") (pin "P1") (pinfunction "1_P1") (pintype "passive"))
      (node (ref "J3") (pin "P1") (pinfunction "1_P1") (pintype "passive"))
      (node (ref "J4") (pin "P1") (pinfunction "1_P1") (pintype "passive"))
      (node (ref "J4") (pin "P2") (pinfunction "2_P2") (pintype "passive"))
      (node (ref "J5") (pin "P1") (pinfunction "1_P1") (pintype "passive"))
      (node (ref "J5") (pin "P2") (pinfunction "2_P2") (pintype "passive"))
      (node (ref "J6") (pin "P1") (pinfunction "1_P1") (pintype "passive"))
      (node (ref "J7") (pin "P1") (pinfunction "1_P1") (pintype "passive"))
      (node (ref "J8") (pin "P1") (pinfunction "1_P1") (pintype "passive"))
      (node (ref "J9") (pin "P1") (pinfunction "1_P1") (pintype "passive"))
      (node (ref "J9") (pin "P2") (pinfunction "2_P2") (pintype "passive"))
      (node (ref "JP1") (pin "3") (pinfunction "3_3") (pintype "passive"))
      (node (ref "JP1") (pin "4") (pinfunction "4_4") (pintype "passive"))
      (node (ref "JP1") (pin "5") (pinfunction "5_5") (pintype "passive"))
      (node (ref "JP1") (pin "6") (pinfunction "6_6") (pintype "passive"))
      (node (ref "JP1") (pin "7") (pinfunction "7_7") (pintype "passive"))
      (node (ref "JP1") (pin "8") (pinfunction "8_8") (pintype "passive"))
      (node (ref "JP2") (pin "3") (pinfunction "3_3") (pintype "passive"))
      (node (ref "JP2") (pin "5") (pinfunction "5_5") (pintype "passive"))
      (node (ref "JP2") (pin "9") (pinfunction "9_9") (pintype "passive"))
      (node (ref "JP3") (pin "1") (pinfunction "1_1") (pintype "passive"))
      (node (ref "LED1") (pin "2") (pinfunction "C_2") (pintype "bidirectional"))
      (node (ref "LED2") (pin "2") (pinfunction "C_2") (pintype "bidirectional"))
      (node (ref "LED3") (pin "2") (pinfunction "C_2") (pintype "bidirectional"))
      (node (ref "Q2") (pin "E") (pinfunction "E_E") (pintype "passive"))
      (node (ref "Q3") (pin "E") (pinfunction "E_E") (pintype "passive"))
      (node (ref "Q4") (pin "E") (pinfunction "E_E") (pintype "passive"))
      (node (ref "Q5") (pin "E") (pinfunction "E_E") (pintype "passive"))
      (node (ref "Q6") (pin "E") (pinfunction "E_E") (pintype "passive"))
      (node (ref "R1") (pin "1") (pinfunction "1_1") (pintype "passive"))
      (node (ref "R17") (pin "P$1") (pinfunction "E_P$1") (pintype "passive"))
      (node (ref "R18") (pin "P$1") (pinfunction "E_P$1") (pintype "passive"))
      (node (ref "R19") (pin "P$1") (pinfunction "E_P$1") (pintype "passive"))
      (node (ref "R26") (pin "1") (pinfunction "1_1") (pintype "passive"))
      (node (ref "R50") (pin "1") (pinfunction "1_1") (pintype "passive"))
      (node (ref "R52") (pin "1") (pinfunction "1_1") (pintype "passive"))
      (node (ref "R6") (pin "P$3") (pinfunction "A_P$3") (pintype "passive"))
      (node (ref "R8") (pin "1") (pinfunction "1_1") (pintype "passive"))
      (node (ref "SW2") (pin "A") (pinfunction "P_A") (pintype "passive"))
      (node (ref "SW2") (pin "A'") (pinfunction "P1_A'") (pintype "passive"))
      (node (ref "SW3") (pin "B1") (pinfunction "P_B1") (pintype "passive"))
      (node (ref "SW3") (pin "B2") (pinfunction "P1_B2") (pintype "passive"))
      (node (ref "SW4") (pin "B1") (pinfunction "P_B1") (pintype "passive"))
      (node (ref "SW4") (pin "B2") (pinfunction "P1_B2") (pintype "passive"))
      (node (ref "UC1") (pin "20") (pinfunction "PB2/BOOT1_20") (pintype "bidirectional"))
      (node (ref "UC1") (pin "23") (pinfunction "VSS_1_23") (pintype "power_in"))
      (node (ref "UC1") (pin "35") (pinfunction "VSS_2_35") (pintype "power_in"))
      (node (ref "UC1") (pin "47") (pinfunction "VSS_3_47") (pintype "power_in"))
      (node (ref "UC1") (pin "8") (pinfunction "VSS_A_8") (pintype "power_in"))
    )
    (net (code "19") (name "JTCK") (class "Default")
      (node (ref "JP2") (pin "4") (pinfunction "4_4") (pintype "passive"))
      (node (ref "UC1") (pin "37") (pinfunction "PA14/JTCK/SWCLK_37") (pintype "bidirectional"))
    )
    (net (code "20") (name "JTDI") (class "Default")
      (node (ref "JP2") (pin "8") (pinfunction "8_8") (pintype "passive"))
      (node (ref "UC1") (pin "38") (pinfunction "PA15/JTDI_38") (pintype "bidirectional"))
    )
    (net (code "21") (name "JTDO") (class "Default")
      (node (ref "JP2") (pin "6") (pinfunction "6_6") (pintype "passive"))
      (node (ref "UC1") (pin "39") (pinfunction "PB3/JTDO_39") (pintype "bidirectional"))
    )
    (net (code "22") (name "JTMS") (class "Default")
      (node (ref "JP2") (pin "2") (pinfunction "2_2") (pintype "passive"))
      (node (ref "UC1") (pin "34") (pinfunction "PA13/JTMS/SWDIO_34") (pintype "bidirectional"))
    )
    (net (code "23") (name "LEVEL_ADC") (class "Default")
      (node (ref "C34") (pin "2") (pinfunction "2_2") (pintype "passive"))
      (node (ref "IC9") (pin "7") (pinfunction "OUT_7") (pintype "output"))
      (node (ref "R45") (pin "1") (pinfunction "1_1") (pintype "passive"))
      (node (ref "UC1") (pin "16") (pinfunction "PA6/SPI1_MISO/ADC12_IN6/TIM3_CH1_16") (pintype "bidirectional"))
    )
    (net (code "24") (name "Net-(C19-Pad1)") (class "Default")
      (node (ref "C19") (pin "1") (pinfunction "1_1") (pintype "passive"))
      (node (ref "R13") (pin "1") (pinfunction "1_1") (pintype "passive"))
      (node (ref "R15") (pin "2") (pinfunction "2_2") (pintype "passive"))
    )
    (net (code "25") (name "Net-(C21-Pad1)") (class "Default")
      (node (ref "C21") (pin "1") (pinfunction "1_1") (pintype "passive"))
      (node (ref "R14") (pin "1") (pinfunction "1_1") (pintype "passive"))
      (node (ref "R16") (pin "2") (pinfunction "2_2") (pintype "passive"))
    )
    (net (code "26") (name "Net-(D1-PadA)") (class "Default")
      (node (ref "D1") (pin "A") (pinfunction "A_A") (pintype "passive"))
      (node (ref "JP1") (pin "1") (pinfunction "1_1") (pintype "passive"))
      (node (ref "JP1") (pin "2") (pinfunction "2_2") (pintype "passive"))
    )
    (net (code "27") (name "Net-(D2-PadC)") (class "Default")
      (node (ref "D2") (pin "C") (pinfunction "C_C") (pintype "passive"))
      (node (ref "JP1") (pin "10") (pinfunction "10_10") (pintype "passive"))
      (node (ref "JP1") (pin "9") (pinfunction "9_9") (pintype "passive"))
    )
    (net (code "28") (name "Net-(IC5A--IN)") (class "Default")
      (node (ref "IC5") (pin "2") (pinfunction "-IN_2") (pintype "input"))
      (node (ref "R20") (pin "1") (pinfunction "1_1") (pintype "passive"))
      (node (ref "R21") (pin "1") (pinfunction "1_1") (pintype "passive"))
      (node (ref "R23") (pin "2") (pinfunction "2_2") (pintype "passive"))
    )
    (net (code "29") (name "Net-(IC5A-OUT)") (class "Default")
      (node (ref "IC5") (pin "1") (pinfunction "OUT_1") (pintype "output"))
      (node (ref "R22") (pin "2") (pinfunction "2_2") (pintype "passive"))
      (node (ref "R23") (pin "1") (pinfunction "1_1") (pintype "passive"))
    )
    (net (code "30") (name "Net-(IC5B-+IN)") (class "Default")
      (node (ref "C22") (pin "1") (pinfunction "1_1") (pintype "passive"))
      (node (ref "IC5") (pin "5") (pinfunction "+IN_5") (pintype "input"))
      (node (ref "R15") (pin "1") (pinfunction "1_1") (pintype "passive"))
    )
    (net (code "31") (name "Net-(IC5B--IN)") (class "Default")
      (node (ref "C19") (pin "2") (pinfunction "2_2") (pintype "passive"))
      (node (ref "IC5") (pin "6") (pinfunction "-IN_6") (pintype "input"))
      (node (ref "IC5") (pin "7") (pinfunction "OUT_7") (pintype "output"))
      (node (ref "R20") (pin "2") (pinfunction "2_2") (pintype "passive"))
    )
    (net (code "32") (name "Net-(IC6A-+IN)") (class "Default")
      (node (ref "C21") (pin "2") (pinfunction "2_2") (pintype "passive"))
      (node (ref "IC6") (pin "3") (pinfunction "+IN_3") (pintype "input"))
      (node (ref "IC6") (pin "6") (pinfunction "-IN_6") (pintype "input"))
      (node (ref "IC6") (pin "7") (pinfunction "OUT_7") (pintype "output"))
    )
    (net (code "33") (name "Net-(IC6A--IN)") (class "Default")
      (node (ref "IC6") (pin "2") (pinfunction "-IN_2") (pintype "input"))
      (node (ref "R25") (pin "2") (pinfunction "2_2") (pintype "passive"))
      (node (ref "R26") (pin "2") (pinfunction "2_2") (pintype "passive"))
    )
    (net (code "34") (name "Net-(IC6A-OUT)") (class "Default")
      (node (ref "IC6") (pin "1") (pinfunction "OUT_1") (pintype "output"))
      (node (ref "R24") (pin "2") (pinfunction "2_2") (pintype "passive"))
      (node (ref "R25") (pin "1") (pinfunction "1_1") (pintype "passive"))
    )
    (net (code "35") (name "Net-(IC6B-+IN)") (class "Default")
      (node (ref "C23") (pin "1") (pinfunction "1_1") (pintype "passive"))
      (node (ref "IC6") (pin "5") (pinfunction "+IN_5") (pintype "input"))
      (node (ref "R16") (pin "1") (pinfunction "1_1") (pintype "passive"))
    )
    (net (code "36") (name "Net-(IC8A--IN)") (class "Default")
      (node (ref "C31") (pin "1") (pinfunction "1_1") (pintype "passive"))
      (node (ref "IC8") (pin "2") (pinfunction "-IN_2") (pintype "input"))
      (node (ref "R37") (pin "2") (pinfunction "2_2") (pintype "passive"))
      (node (ref "R38") (pin "1") (pinfunction "1_1") (pintype "passive"))
      (node (ref "R39") (pin "1") (pinfunction "1_1") (pintype "passive"))
    )
    (net (code "37") (name "Net-(IC8B--IN)") (class "Default")
      (node (ref "C27") (pin "1") (pinfunction "1_1") (pintype "passive"))
      (node (ref "IC8") (pin "6") (pinfunction "-IN_6") (pintype "input"))
      (node (ref "R34") (pin "2") (pinfunction "2_2") (pintype "passive"))
      (node (ref "R35") (pin "1") (pinfunction "1_1") (pintype "passive"))
      (node (ref "R36") (pin "1") (pinfunction "1_1") (pintype "passive"))
    )
    (net (code "38") (name "Net-(IC9A--IN)") (class "Default")
      (node (ref "C32") (pin "1") (pinfunction "1_1") (pintype "passive"))
      (node (ref "IC9") (pin "2") (pinfunction "-IN_2") (pintype "input"))
      (node (ref "R40") (pin "2") (pinfunction "2_2") (pintype "passive"))
      (node (ref "R41") (pin "1") (pinfunction "1_1") (pintype "passive"))
      (node (ref "R42") (pin "1") (pinfunction "1_1") (pintype "passive"))
    )
    (net (code "39") (name "Net-(IC9B--IN)") (class "Default")
      (node (ref "C34") (pin "1") (pinfunction "1_1") (pintype "passive"))
      (node (ref "IC9") (pin "6") (pinfunction "-IN_6") (pintype "input"))
      (node (ref "R43") (pin "1") (pinfunction "1_1") (pintype "passive"))
      (node (ref "R44") (pin "1") (pinfunction "1_1") (pintype "passive"))
      (node (ref "R45") (pin "2") (pinfunction "2_2") (pintype "passive"))
    )
    (net (code "40") (name "Net-(IC9C--IN)") (class "Default")
      (node (ref "C28") (pin "1") (pinfunction "1_1") (pintype "passive"))
      (node (ref "IC9") (pin "9") (pinfunction "-IN_9") (pintype "input"))
      (node (ref "R31") (pin "1") (pinfunction "1_1") (pintype "passive"))
      (node (ref "R32") (pin "1") (pinfunction "1_1") (pintype "passive"))
      (node (ref "R33") (pin "2") (pinfunction "2_2") (pintype "passive"))
    )
    (net (code "41") (name "Net-(IC9D--IN)") (class "Default")
      (node (ref "C29") (pin "1") (pinfunction "1_1") (pintype "passive"))
      (node (ref "IC9") (pin "13") (pinfunction "-IN_13") (pintype "input"))
      (node (ref "R28") (pin "2") (pinfunction "2_2") (pintype "passive"))
      (node (ref "R29") (pin "1") (pinfunction "1_1") (pintype "passive"))
      (node (ref "R30") (pin "1") (pinfunction "1_1") (pintype "passive"))
    )
    (net (code "42") (name "Net-(J1-3)") (class "Default")
      (node (ref "J1") (pin "P3") (pinfunction "3_P3") (pintype "passive"))
      (node (ref "R42") (pin "2") (pinfunction "2_2") (pintype "passive"))
    )
    (net (code "43") (name "Net-(J2-3)") (class "Default")
      (node (ref "J2") (pin "P3") (pinfunction "3_P3") (pintype "passive"))
      (node (ref "R29") (pin "2") (pinfunction "2_2") (pintype "passive"))
    )
    (net (code "44") (name "Net-(J3-3)") (class "Default")
      (node (ref "J3") (pin "P3") (pinfunction "3_P3") (pintype "passive"))
      (node (ref "R32") (pin "2") (pinfunction "2_2") (pintype "passive"))
    )
    (net (code "45") (name "Net-(J4-3)") (class "Default")
      (node (ref "J4") (pin "P3") (pinfunction "3_P3") (pintype "passive"))
      (node (ref "R55") (pin "1") (pinfunction "1_1") (pintype "passive"))
    )
    (net (code "46") (name "Net-(J5-3)") (class "Default")
      (node (ref "J5") (pin "P3") (pinfunction "3_P3") (pintype "passive"))
      (node (ref "R56") (pin "1") (pinfunction "1_1") (pintype "passive"))
    )
    (net (code "47") (name "Net-(J6-3)") (class "Default")
      (node (ref "J6") (pin "P3") (pinfunction "3_P3") (pintype "passive"))
      (node (ref "R39") (pin "2") (pinfunction "2_2") (pintype "passive"))
    )
    (net (code "48") (name "Net-(J7-2)") (class "Default")
      (node (ref "J7") (pin "P2") (pinfunction "2_P2") (pintype "passive"))
      (node (ref "R46") (pin "1") (pinfunction "1_1") (pintype "passive"))
    )
    (net (code "49") (name "Net-(J7-3)") (class "Default")
      (node (ref "J7") (pin "P3") (pinfunction "3_P3") (pintype "passive"))
      (node (ref "R36") (pin "2") (pinfunction "2_2") (pintype "passive"))
    )
    (net (code "50") (name "Net-(J8-2)") (class "Default")
      (node (ref "J8") (pin "P2") (pinfunction "2_P2") (pintype "passive"))
      (node (ref "R60") (pin "2") (pinfunction "2_2") (pintype "passive"))
    )
    (net (code "51") (name "Net-(J8-3)") (class "Default")
      (node (ref "J8") (pin "P3") (pinfunction "3_P3") (pintype "passive"))
      (node (ref "R44") (pin "2") (pinfunction "2_2") (pintype "passive"))
    )
    (net (code "52") (name "Net-(J9-3)") (class "Default")
      (node (ref "J9") (pin "P3") (pinfunction "3_P3") (pintype "passive"))
      (node (ref "R54") (pin "1") (pinfunction "1_1") (pintype "passive"))
    )
    (net (code "53") (name "Net-(J10-3)") (class "Default")
      (node (ref "J10") (pin "P3") (pinfunction "3_P3") (pintype "passive"))
      (node (ref "Q5") (pin "C") (pinfunction "C_C") (pintype "passive"))
      (node (ref "R50") (pin "2") (pinfunction "2_2") (pintype "passive"))
      (node (ref "R51") (pin "1") (pinfunction "1_1") (pintype "passive"))
    )
    (net (code "54") (name "Net-(J11-3)") (class "Default")
      (node (ref "J11") (pin "P3") (pinfunction "3_P3") (pintype "passive"))
      (node (ref "Q6") (pin "C") (pinfunction "C_C") (pintype "passive"))
      (node (ref "R52") (pin "2") (pinfunction "2_2") (pintype "passive"))
      (node (ref "R53") (pin "1") (pinfunction "1_1") (pintype "passive"))
    )
    (net (code "55") (name "Net-(J12-3)") (class "Default")
      (node (ref "J12") (pin "P3") (pinfunction "3_P3") (pintype "passive"))
      (node (ref "R24") (pin "1") (pinfunction "1_1") (pintype "passive"))
    )
    (net (code "56") (name "Net-(J13-3)") (class "Default")
      (node (ref "J13") (pin "P3") (pinfunction "3_P3") (pintype "passive"))
      (node (ref "R22") (pin "1") (pinfunction "1_1") (pintype "passive"))
    )
    (net (code "57") (name "Net-(LED1-GRN)") (class "Default")
      (node (ref "LED1") (pin "1") (pinfunction "GRN_1") (pintype "bidirectional"))
      (node (ref "R2") (pin "2") (pinfunction "2_2") (pintype "passive"))
    )
    (net (code "58") (name "Net-(LED1-RED)") (class "Default")
      (node (ref "LED1") (pin "3") (pinfunction "RED_3") (pintype "bidirectional"))
      (node (ref "R3") (pin "2") (pinfunction "2_2") (pintype "passive"))
    )
    (net (code "59") (name "Net-(LED2-GRN)") (class "Default")
      (node (ref "LED2") (pin "1") (pinfunction "GRN_1") (pintype "bidirectional"))
      (node (ref "R4") (pin "2") (pinfunction "2_2") (pintype "passive"))
    )
    (net (code "60") (name "Net-(LED2-RED)") (class "Default")
      (node (ref "LED2") (pin "3") (pinfunction "RED_3") (pintype "bidirectional"))
      (node (ref "R7") (pin "2") (pinfunction "2_2") (pintype "passive"))
    )
    (net (code "61") (name "Net-(LED3-GRN)") (class "Default")
      (node (ref "LED3") (pin "1") (pinfunction "GRN_1") (pintype "bidirectional"))
      (node (ref "R9") (pin "2") (pinfunction "2_2") (pintype "passive"))
    )
    (net (code "62") (name "Net-(LED3-RED)") (class "Default")
      (node (ref "LED3") (pin "3") (pinfunction "RED_3") (pintype "bidirectional"))
      (node (ref "R10") (pin "2") (pinfunction "2_2") (pintype "passive"))
    )
    (net (code "63") (name "Net-(Q2-PadB)") (class "Default")
      (node (ref "Q2") (pin "B") (pinfunction "B_B") (pintype "passive"))
      (node (ref "R55") (pin "2") (pinfunction "2_2") (pintype "passive"))
    )
    (net (code "64") (name "Net-(Q3-PadB)") (class "Default")
      (node (ref "Q3") (pin "B") (pinfunction "B_B") (pintype "passive"))
      (node (ref "R54") (pin "2") (pinfunction "2_2") (pintype "passive"))
    )
    (net (code "65") (name "Net-(Q4-PadB)") (class "Default")
      (node (ref "Q4") (pin "B") (pinfunction "B_B") (pintype "passive"))
      (node (ref "R56") (pin "2") (pinfunction "2_2") (pintype "passive"))
    )
    (net (code "66") (name "Net-(Q5-PadB)") (class "Default")
      (node (ref "Q5") (pin "B") (pinfunction "B_B") (pintype "passive"))
      (node (ref "R57") (pin "2") (pinfunction "2_2") (pintype "passive"))
    )
    (net (code "67") (name "Net-(Q6-PadB)") (class "Default")
      (node (ref "Q6") (pin "B") (pinfunction "B_B") (pintype "passive"))
      (node (ref "R58") (pin "2") (pinfunction "2_2") (pintype "passive"))
    )
    (net (code "68") (name "Net-(R5-E)") (class "Default")
      (node (ref "R5") (pin "P$1") (pinfunction "E_P$1") (pintype "passive"))
      (node (ref "R8") (pin "2") (pinfunction "2_2") (pintype "passive"))
    )
    (net (code "69") (name "Net-(R5-S)") (class "Default")
      (node (ref "R38") (pin "2") (pinfunction "2_2") (pintype "passive"))
      (node (ref "R5") (pin "P$2") (pinfunction "S_P$2") (pintype "passive"))
    )
    (net (code "70") (name "Net-(R17-S)") (class "Default")
      (node (ref "R17") (pin "P$2") (pinfunction "S_P$2") (pintype "passive"))
      (node (ref "R41") (pin "2") (pinfunction "2_2") (pintype "passive"))
    )
    (net (code "71") (name "Net-(R18-S)") (class "Default")
      (node (ref "R18") (pin "P$2") (pinfunction "S_P$2") (pintype "passive"))
      (node (ref "R30") (pin "2") (pinfunction "2_2") (pintype "passive"))
    )
    (net (code "72") (name "Net-(R19-S)") (class "Default")
      (node (ref "R19") (pin "P$2") (pinfunction "S_P$2") (pintype "passive"))
      (node (ref "R31") (pin "2") (pinfunction "2_2") (pintype "passive"))
    )
    (net (code "73") (name "Net-(R59-E)") (class "Default")
      (node (ref "R21") (pin "2") (pinfunction "2_2") (pintype "passive"))
      (node (ref "R59") (pin "1") (pinfunction "E_1") (pintype "passive"))
    )
    (net (code "74") (name "Net-(UC1-PB4{slash}NJTRST)") (class "Default")
      (node (ref "R2") (pin "1") (pinfunction "1_1") (pintype "passive"))
      (node (ref "UC1") (pin "40") (pinfunction "PB4/NJTRST_40") (pintype "bidirectional"))
    )
    (net (code "75") (name "Net-(UC1-PB5{slash}I2C1_SMBA)") (class "Default")
      (node (ref "R3") (pin "1") (pinfunction "1_1") (pintype "passive"))
      (node (ref "UC1") (pin "41") (pinfunction "PB5/I2C1_SMBA_41") (pintype "input"))
    )
    (net (code "76") (name "Net-(UC1-PB6{slash}I2C1_SCL{slash}TIM4_CH1)") (class "Default")
      (node (ref "R4") (pin "1") (pinfunction "1_1") (pintype "passive"))
      (node (ref "UC1") (pin "42") (pinfunction "PB6/I2C1_SCL/TIM4_CH1_42") (pintype "input"))
    )
    (net (code "77") (name "Net-(UC1-PB7{slash}I2C1_SDA{slash}TIM4_CH2)") (class "Default")
      (node (ref "R7") (pin "1") (pinfunction "1_1") (pintype "passive"))
      (node (ref "UC1") (pin "43") (pinfunction "PB7/I2C1_SDA/TIM4_CH2_43") (pintype "bidirectional"))
    )
    (net (code "78") (name "Net-(UC1-PB8{slash}TIM4_CH3)") (class "Default")
      (node (ref "R9") (pin "1") (pinfunction "1_1") (pintype "passive"))
      (node (ref "UC1") (pin "45") (pinfunction "PB8/TIM4_CH3_45") (pintype "bidirectional"))
    )
    (net (code "79") (name "Net-(UC1-PB9{slash}TIM4_CH4)") (class "Default")
      (node (ref "R10") (pin "1") (pinfunction "1_1") (pintype "passive"))
      (node (ref "UC1") (pin "46") (pinfunction "PB9/TIM4_CH4_46") (pintype "input"))
    )
    (net (code "80") (name "Net-(UC1-PD0-OSC_IN)") (class "Default")
      (node (ref "C2") (pin "2") (pinfunction "2_2") (pintype "passive"))
      (node (ref "Q1") (pin "2") (pinfunction "2_2") (pintype "passive"))
      (node (ref "UC1") (pin "5") (pinfunction "PD0-OSC_IN_5") (pintype "input"))
    )
    (net (code "81") (name "Net-(UC1-PD1-OSC_OUT)") (class "Default")
      (node (ref "C17") (pin "2") (pinfunction "2_2") (pintype "passive"))
      (node (ref "Q1") (pin "1") (pinfunction "1_1") (pintype "passive"))
      (node (ref "UC1") (pin "6") (pinfunction "PD1-OSC_OUT_6") (pintype "input"))
    )
    (net (code "82") (name "PROC_ADC") (class "Default")
      (node (ref "C28") (pin "2") (pinfunction "2_2") (pintype "passive"))
      (node (ref "IC9") (pin "8") (pinfunction "OUT_8") (pintype "output"))
      (node (ref "R33") (pin "1") (pinfunction "1_1") (pintype "passive"))
      (node (ref "UC1") (pin "17") (pinfunction "PA7/SPI1_MOSI/ADC12_IN7/TIM3_CH2_17") (pintype "bidirectional"))
    )
    (net (code "83") (name "RANGE_SW") (class "Default")
      (node (ref "SW4") (pin "A1") (pinfunction "S_A1") (pintype "passive"))
      (node (ref "SW4") (pin "A2") (pinfunction "S1_A2") (pintype "passive"))
      (node (ref "UC1") (pin "11") (pinfunction "PA1/USART2_RTS/ADC12_IN1/TIM2_CH2_11") (pintype "bidirectional"))
    )
    (net (code "84") (name "RESET") (class "Default")
      (node (ref "JP2") (pin "10") (pinfunction "10_10") (pintype "passive"))
      (node (ref "R11") (pin "1") (pinfunction "1_1") (pintype "passive"))
      (node (ref "SW2") (pin "B") (pinfunction "S_B") (pintype "passive"))
      (node (ref "SW2") (pin "B'") (pinfunction "S1_B'") (pintype "passive"))
      (node (ref "UC1") (pin "7") (pinfunction "NRST_7") (pintype "input"))
    )
    (net (code "85") (name "RX") (class "Default")
      (node (ref "JP3") (pin "4") (pinfunction "4_4") (pintype "passive"))
      (node (ref "UC1") (pin "31") (pinfunction "PA10/USART1_RX/TIM1_CH3_31") (pintype "bidirectional"))
    )
    (net (code "86") (name "SHAPE_ADC") (class "Default")
      (node (ref "C32") (pin "2") (pinfunction "2_2") (pintype "passive"))
      (node (ref "IC9") (pin "1") (pinfunction "OUT_1") (pintype "output"))
      (node (ref "R40") (pin "1") (pinfunction "1_1") (pintype "passive"))
      (node (ref "UC1") (pin "15") (pinfunction "PA5/SPI1_SCK/ADC12_IN5_15") (pintype "bidirectional"))
    )
    (net (code "87") (name "START") (class "Default")
      (node (ref "Q2") (pin "C") (pinfunction "C_C") (pintype "passive"))
      (node (ref "R47") (pin "1") (pinfunction "1_1") (pintype "passive"))
      (node (ref "UC1") (pin "22") (pinfunction "PB11/I2C2_SDA/USART3_RX_22") (pintype "input"))
    )
    (net (code "88") (name "TX") (class "Default")
      (node (ref "JP3") (pin "5") (pinfunction "5_5") (pintype "passive"))
      (node (ref "UC1") (pin "30") (pinfunction "PA9/USART1_TX/TIM1_CH2_30") (pintype "input"))
    )
    (net (code "89") (name "UNI") (class "Default")
      (node (ref "IC4") (pin "4") (pinfunction "OUTA_4") (pintype "output"))
      (node (ref "R14") (pin "2") (pinfunction "2_2") (pintype "passive"))
    )
    (net (code "90") (name "VCC") (class "Default")
      (node (ref "C18") (pin "1") (pinfunction "1_1") (pintype "passive"))
      (node (ref "C20") (pin "1") (pinfunction "1_1") (pintype "passive"))
      (node (ref "C3") (pin "+") (pinfunction "+_+") (pintype "passive"))
      (node (ref "C8") (pin "+") (pinfunction "+_+") (pintype "passive"))
      (node (ref "D1") (pin "C") (pinfunction "C_C") (pintype "passive"))
      (node (ref "IC1") (pin "3") (pinfunction "VIN_3") (pintype "input"))
      (node (ref "IC3") (pin "3") (pinfunction "VIN_3") (pintype "input"))
      (node (ref "IC5") (pin "8") (pinfunction "V+_8") (pintype "power_in"))
      (node (ref "IC6") (pin "8") (pinfunction "V+_8") (pintype "power_in"))
      (node (ref "R51") (pin "2") (pinfunction "2_2") (pintype "passive"))
      (node (ref "R53") (pin "2") (pinfunction "2_2") (pintype "passive"))
      (node (ref "R60") (pin "1") (pinfunction "1_1") (pintype "passive"))
    )
    (net (code "91") (name "VEE") (class "Default")
      (node (ref "C10") (pin "-") (pinfunction "-_-") (pintype "passive"))
      (node (ref "C24") (pin "2") (pinfunction "2_2") (pintype "passive"))
      (node (ref "C25") (pin "2") (pinfunction "2_2") (pintype "passive"))
      (node (ref "D2") (pin "A") (pinfunction "A_A") (pintype "passive"))
      (node (ref "IC5") (pin "4") (pinfunction "V-_4") (pintype "power_in"))
      (node (ref "IC6") (pin "4") (pinfunction "V-_4") (pintype "power_in"))
      (node (ref "R27") (pin "1") (pinfunction "1_1") (pintype "passive"))
    )
    (net (code "92") (name "VOCT_ADC") (class "Default")
      (node (ref "C31") (pin "2") (pinfunction "2_2") (pintype "passive"))
      (node (ref "IC8") (pin "1") (pinfunction "OUT_1") (pintype "output"))
      (node (ref "R37") (pin "1") (pinfunction "1_1") (pintype "passive"))
      (node (ref "UC1") (pin "13") (pinfunction "PA3/USART2_RX/ADC12_IN3/TIM2_CH4_13") (pintype "bidirectional"))
    )
    (net (code "93") (name "unconnected-(J1-2-PadP2)") (class "Default")
      (node (ref "J1") (pin "P2") (pinfunction "2_P2") (pintype "passive"))
    )
    (net (code "94") (name "unconnected-(J2-2-PadP2)") (class "Default")
      (node (ref "J2") (pin "P2") (pinfunction "2_P2") (pintype "passive"))
    )
    (net (code "95") (name "unconnected-(J3-2-PadP2)") (class "Default")
      (node (ref "J3") (pin "P2") (pinfunction "2_P2") (pintype "passive"))
    )
    (net (code "96") (name "unconnected-(J6-2-PadP2)") (class "Default")
      (node (ref "J6") (pin "P2") (pinfunction "2_P2") (pintype "passive"))
    )
    (net (code "97") (name "unconnected-(J10-2-PadP2)") (class "Default")
      (node (ref "J10") (pin "P2") (pinfunction "2_P2") (pintype "passive"))
    )
    (net (code "98") (name "unconnected-(J11-2-PadP2)") (class "Default")
      (node (ref "J11") (pin "P2") (pinfunction "2_P2") (pintype "passive"))
    )
    (net (code "99") (name "unconnected-(J12-2-PadP2)") (class "Default")
      (node (ref "J12") (pin "P2") (pinfunction "2_P2") (pintype "passive"))
    )
    (net (code "100") (name "unconnected-(J13-2-PadP2)") (class "Default")
      (node (ref "J13") (pin "P2") (pinfunction "2_P2") (pintype "passive"))
    )
    (net (code "101") (name "unconnected-(JP2-Pad7)") (class "Default")
      (node (ref "JP2") (pin "7") (pinfunction "7_7") (pintype "passive"))
    )
    (net (code "102") (name "unconnected-(JP3-Pad2)") (class "Default")
      (node (ref "JP3") (pin "2") (pinfunction "2_2") (pintype "passive"))
    )
    (net (code "103") (name "unconnected-(JP3-Pad3)") (class "Default")
      (node (ref "JP3") (pin "3") (pinfunction "3_3") (pintype "passive"))
    )
    (net (code "104") (name "unconnected-(JP3-Pad6)") (class "Default")
      (node (ref "JP3") (pin "6") (pinfunction "6_6") (pintype "passive"))
    )
    (net (code "105") (name "unconnected-(UC1-PA8{slash}USART1_CK{slash}TIM1_CH1{slash}MCO-Pad29)") (class "Default")
      (node (ref "UC1") (pin "29") (pinfunction "PA8/USART1_CK/TIM1_CH1/MCO_29") (pintype "bidirectional"))
    )
    (net (code "106") (name "unconnected-(UC1-PB14{slash}SPI2_MISO{slash}USART3_RTS{slash}TIM1_CH2N-Pad27)") (class "Default")
      (node (ref "UC1") (pin "27") (pinfunction "PB14/SPI2_MISO/USART3_RTS/TIM1_CH2N_27") (pintype "input"))
    )
    (net (code "107") (name "unconnected-(UC1-PC13-TAMPER-RTC-Pad2)") (class "Default")
      (node (ref "UC1") (pin "2") (pinfunction "PC13-TAMPER-RTC_2") (pintype "input"))
    )
    (net (code "108") (name "unconnected-(UC1-PC14-OSC32_IN-Pad3)") (class "Default")
      (node (ref "UC1") (pin "3") (pinfunction "PC14-OSC32_IN_3") (pintype "input"))
    )
    (net (code "109") (name "unconnected-(UC1-PC15-OSC32_OUT-Pad4)") (class "Default")
      (node (ref "UC1") (pin "4") (pinfunction "PC15-OSC32_OUT_4") (pintype "input"))
    )
  )
)
